# mega328_withheaders_andxbee_v2.net
KiCad netlist of a schematic drawn in EAGLE
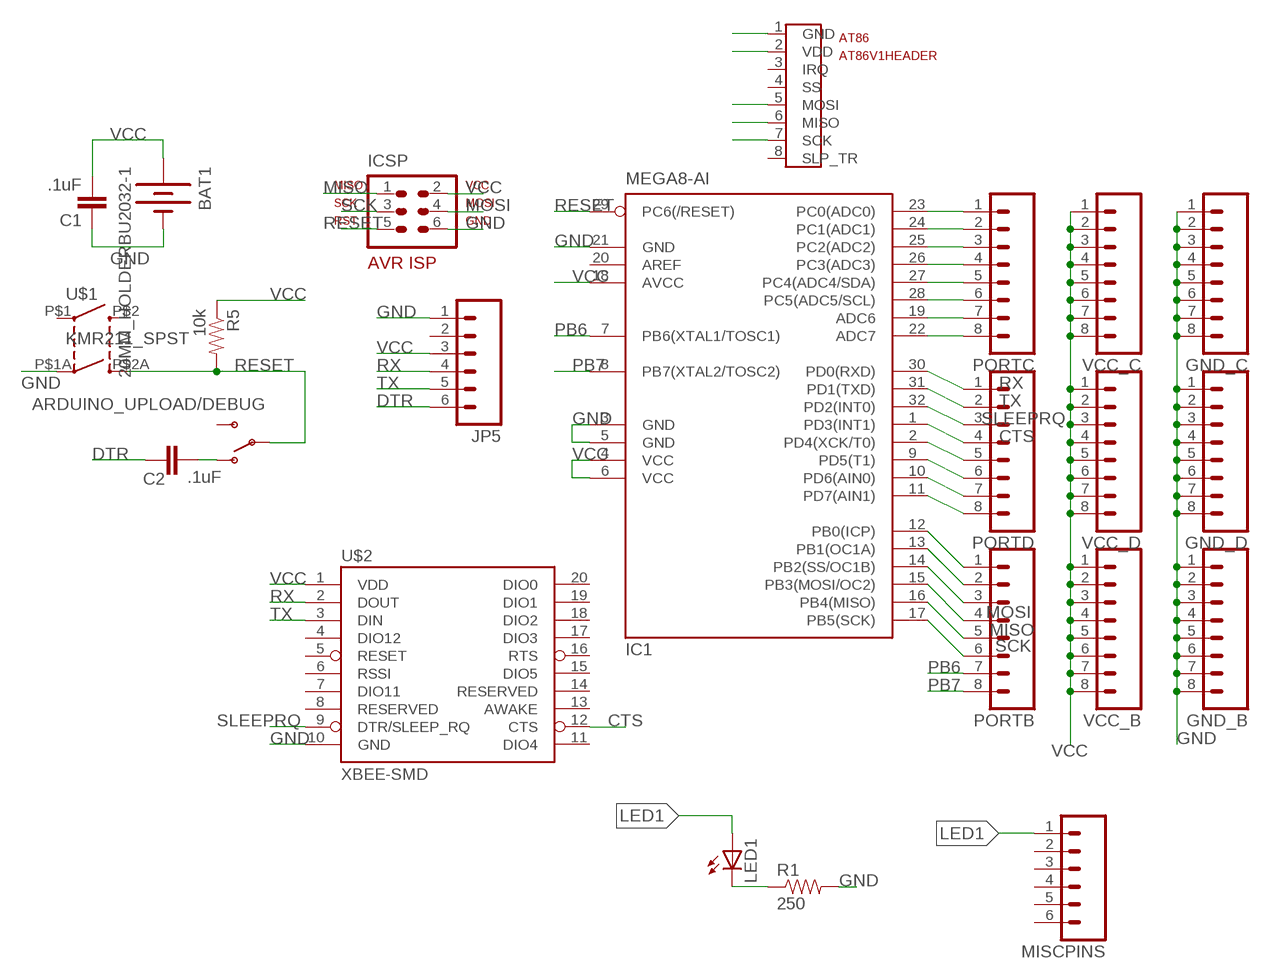
[diagram p0: schematic, sheet 1]

(export (version "E")
  (design (tool "Eeschema 10.0.6"))
  (components
    (comp (ref "ARDUINO_UPLOAD/DEBUG")
      (value "SWITCH-SPDT-SMD-A")
      (footprint "eagle-import:SWITCH-SPST-SMD-A")
      (libsource (lib "eagle-import") (part "SWITCH-SPDT-SMD-A"))
    )
    (comp (ref "AT86")
      (value "AT86V1HEADER")
      (footprint "eagle-import:AT86V1HEADER")
      (libsource (lib "eagle-import") (part "AT86V1HEADER"))
    )
    (comp (ref "BAT1")
      (value "20MM_HOLDERBU2032-1")
      (footprint "eagle-import:BU2032-1")
      (libsource (lib "eagle-import") (part "20MM_HOLDERBU2032-1"))
    )
    (comp (ref "C1")
      (value ".1uF")
      (footprint "eagle-import:0603-CAP")
      (libsource (lib "eagle-import") (part "CAP0603-CAP"))
    )
    (comp (ref "C2")
      (value ".1uF")
      (footprint "eagle-import:0603-CAP")
      (libsource (lib "eagle-import") (part "CAP0603-CAP"))
    )
    (comp (ref "GND_B")
      (value "M081X08")
      (footprint "eagle-import:1X08")
      (libsource (lib "eagle-import") (part "M081X08"))
    )
    (comp (ref "GND_C")
      (value "M081X08")
      (footprint "eagle-import:1X08")
      (libsource (lib "eagle-import") (part "M081X08"))
    )
    (comp (ref "GND_D")
      (value "M081X08")
      (footprint "eagle-import:1X08")
      (libsource (lib "eagle-import") (part "M081X08"))
    )
    (comp (ref "IC1")
      (value "MEGA8-AI")
      (footprint "eagle-import:TQFP32-08")
      (fields (field (name "MPN") "ATMEGA8-16AU"))
      (libsource (lib "eagle-import") (part "MEGA8-AI"))
    )
    (comp (ref "ICSP")
      (value "ISP")
      (footprint "eagle-import:AVR-ISP-6")
      (libsource (lib "eagle-import") (part "AVR-ISP-6VERT"))
    )
    (comp (ref "JP5")
      (value "M06SIP")
      (footprint "eagle-import:1X06")
      (libsource (lib "eagle-import") (part "M06SIP"))
    )
    (comp (ref "LED1")
      (value "LEDCHIP-LED0603")
      (footprint "eagle-import:CHIP-LED0603")
      (libsource (lib "eagle-import") (part "LEDCHIP-LED0603"))
    )
    (comp (ref "MISCPINS")
      (value "M06SIP")
      (footprint "eagle-import:1X06")
      (libsource (lib "eagle-import") (part "M06SIP"))
    )
    (comp (ref "PORTB")
      (value "M081X08")
      (footprint "eagle-import:1X08")
      (libsource (lib "eagle-import") (part "M081X08"))
    )
    (comp (ref "PORTC")
      (value "M081X08")
      (footprint "eagle-import:1X08")
      (libsource (lib "eagle-import") (part "M081X08"))
    )
    (comp (ref "PORTD")
      (value "M081X08")
      (footprint "eagle-import:1X08")
      (libsource (lib "eagle-import") (part "M081X08"))
    )
    (comp (ref "R1")
      (value "250")
      (footprint "eagle-import:0603-RES")
      (libsource (lib "eagle-import") (part "RESISTOR0603-RES"))
    )
    (comp (ref "R5")
      (value "10k")
      (footprint "eagle-import:0603-RES")
      (libsource (lib "eagle-import") (part "RESISTOR0603-RES"))
    )
    (comp (ref "U$1")
      (value "KMR211_SPST")
      (footprint "eagle-import:KMR211_SPST")
      (libsource (lib "eagle-import") (part "KMR211_SPST"))
    )
    (comp (ref "U$2")
      (value "XBEE-SMD")
      (footprint "eagle-import:XBEE-SMD")
      (libsource (lib "eagle-import") (part "XBEE-SMD"))
    )
    (comp (ref "VCC_B")
      (value "M081X08")
      (footprint "eagle-import:1X08")
      (libsource (lib "eagle-import") (part "M081X08"))
    )
    (comp (ref "VCC_C")
      (value "M081X08")
      (footprint "eagle-import:1X08")
      (libsource (lib "eagle-import") (part "M081X08"))
    )
    (comp (ref "VCC_D")
      (value "M081X08")
      (footprint "eagle-import:1X08")
      (libsource (lib "eagle-import") (part "M081X08"))
    )
  )
  (nets
    (net (code "1") (name "/CTS") (class "Default")
      (node (ref "IC1") (pin "1") (pinfunction "PD3(INT1)_1") (pintype "bidirectional"))
      (node (ref "PORTD") (pin "4") (pinfunction "4_4") (pintype "passive"))
      (node (ref "U$2") (pin "12") (pinfunction "CTS_12") (pintype "output"))
    )
    (net (code "2") (name "/DTR") (class "Default")
      (node (ref "C2") (pin "1") (pinfunction "1_1") (pintype "passive"))
      (node (ref "JP5") (pin "6") (pinfunction "6_6") (pintype "passive"))
    )
    (net (code "3") (name "/GND") (class "Default")
      (node (ref "AT86") (pin "1") (pinfunction "GND_1") (pintype "bidirectional"))
      (node (ref "BAT1") (pin "-") (pinfunction "-_-") (pintype "power_in"))
      (node (ref "C1") (pin "1") (pinfunction "1_1") (pintype "passive"))
      (node (ref "GND_B") (pin "1") (pinfunction "1_1") (pintype "passive"))
      (node (ref "GND_B") (pin "2") (pinfunction "2_2") (pintype "passive"))
      (node (ref "GND_B") (pin "3") (pinfunction "3_3") (pintype "passive"))
      (node (ref "GND_B") (pin "4") (pinfunction "4_4") (pintype "passive"))
      (node (ref "GND_B") (pin "5") (pinfunction "5_5") (pintype "passive"))
      (node (ref "GND_B") (pin "6") (pinfunction "6_6") (pintype "passive"))
      (node (ref "GND_B") (pin "7") (pinfunction "7_7") (pintype "passive"))
      (node (ref "GND_B") (pin "8") (pinfunction "8_8") (pintype "passive"))
      (node (ref "GND_C") (pin "1") (pinfunction "1_1") (pintype "passive"))
      (node (ref "GND_C") (pin "2") (pinfunction "2_2") (pintype "passive"))
      (node (ref "GND_C") (pin "3") (pinfunction "3_3") (pintype "passive"))
      (node (ref "GND_C") (pin "4") (pinfunction "4_4") (pintype "passive"))
      (node (ref "GND_C") (pin "5") (pinfunction "5_5") (pintype "passive"))
      (node (ref "GND_C") (pin "6") (pinfunction "6_6") (pintype "passive"))
      (node (ref "GND_C") (pin "7") (pinfunction "7_7") (pintype "passive"))
      (node (ref "GND_C") (pin "8") (pinfunction "8_8") (pintype "passive"))
      (node (ref "GND_D") (pin "1") (pinfunction "1_1") (pintype "passive"))
      (node (ref "GND_D") (pin "2") (pinfunction "2_2") (pintype "passive"))
      (node (ref "GND_D") (pin "3") (pinfunction "3_3") (pintype "passive"))
      (node (ref "GND_D") (pin "4") (pinfunction "4_4") (pintype "passive"))
      (node (ref "GND_D") (pin "5") (pinfunction "5_5") (pintype "passive"))
      (node (ref "GND_D") (pin "6") (pinfunction "6_6") (pintype "passive"))
      (node (ref "GND_D") (pin "7") (pinfunction "7_7") (pintype "passive"))
      (node (ref "GND_D") (pin "8") (pinfunction "8_8") (pintype "passive"))
      (node (ref "IC1") (pin "21") (pinfunction "GND_21") (pintype "power_in"))
      (node (ref "IC1") (pin "3") (pinfunction "GND_3") (pintype "power_in"))
      (node (ref "IC1") (pin "5") (pinfunction "GND_5") (pintype "power_in"))
      (node (ref "ICSP") (pin "6") (pinfunction "6_6") (pintype "passive"))
      (node (ref "JP5") (pin "1") (pinfunction "1_1") (pintype "passive"))
      (node (ref "R1") (pin "2") (pinfunction "2_2") (pintype "passive"))
      (node (ref "U$1") (pin "P$1A") (pinfunction "1B_P$1A") (pintype "passive"))
      (node (ref "U$2") (pin "10") (pinfunction "GND_10") (pintype "power_in"))
    )
    (net (code "4") (name "/MISO") (class "Default")
      (node (ref "AT86") (pin "6") (pinfunction "MISO_6") (pintype "bidirectional"))
      (node (ref "IC1") (pin "16") (pinfunction "PB4(MISO)_16") (pintype "bidirectional"))
      (node (ref "ICSP") (pin "1") (pinfunction "1_1") (pintype "passive"))
      (node (ref "PORTB") (pin "5") (pinfunction "5_5") (pintype "passive"))
    )
    (net (code "5") (name "/MOSI") (class "Default")
      (node (ref "AT86") (pin "5") (pinfunction "MOSI_5") (pintype "bidirectional"))
      (node (ref "IC1") (pin "15") (pinfunction "PB3(MOSI/OC2)_15") (pintype "bidirectional"))
      (node (ref "ICSP") (pin "4") (pinfunction "4_4") (pintype "passive"))
      (node (ref "PORTB") (pin "4") (pinfunction "4_4") (pintype "passive"))
    )
    (net (code "6") (name "/PB6") (class "Default")
      (node (ref "IC1") (pin "7") (pinfunction "PB6(XTAL1/TOSC1)_7") (pintype "bidirectional"))
      (node (ref "PORTB") (pin "7") (pinfunction "7_7") (pintype "passive"))
    )
    (net (code "7") (name "/PB7") (class "Default")
      (node (ref "IC1") (pin "8") (pinfunction "PB7(XTAL2/TOSC2)_8") (pintype "bidirectional"))
      (node (ref "PORTB") (pin "8") (pinfunction "8_8") (pintype "passive"))
    )
    (net (code "8") (name "/RESET") (class "Default")
      (node (ref "ARDUINO_UPLOAD/DEBUG") (pin "2") (pinfunction "P_2") (pintype "passive"))
      (node (ref "IC1") (pin "29") (pinfunction "PC6(/RESET)_29") (pintype "bidirectional"))
      (node (ref "ICSP") (pin "5") (pinfunction "5_5") (pintype "passive"))
      (node (ref "R5") (pin "2") (pinfunction "2_2") (pintype "passive"))
      (node (ref "U$1") (pin "P$2A") (pinfunction "2B_P$2A") (pintype "passive"))
    )
    (net (code "9") (name "/RX") (class "Default")
      (node (ref "IC1") (pin "30") (pinfunction "PD0(RXD)_30") (pintype "bidirectional"))
      (node (ref "JP5") (pin "4") (pinfunction "4_4") (pintype "passive"))
      (node (ref "PORTD") (pin "1") (pinfunction "1_1") (pintype "passive"))
      (node (ref "U$2") (pin "2") (pinfunction "DOUT_2") (pintype "output"))
    )
    (net (code "10") (name "/SCK") (class "Default")
      (node (ref "AT86") (pin "7") (pinfunction "SCK_7") (pintype "bidirectional"))
      (node (ref "IC1") (pin "17") (pinfunction "PB5(SCK)_17") (pintype "bidirectional"))
      (node (ref "ICSP") (pin "3") (pinfunction "3_3") (pintype "passive"))
      (node (ref "PORTB") (pin "6") (pinfunction "6_6") (pintype "passive"))
    )
    (net (code "11") (name "/SLEEPRQ") (class "Default")
      (node (ref "IC1") (pin "32") (pinfunction "PD2(INT0)_32") (pintype "bidirectional"))
      (node (ref "PORTD") (pin "3") (pinfunction "3_3") (pintype "passive"))
      (node (ref "U$2") (pin "9") (pinfunction "DTR/SLEEP_RQ_9") (pintype "bidirectional"))
    )
    (net (code "12") (name "/TX") (class "Default")
      (node (ref "IC1") (pin "31") (pinfunction "PD1(TXD)_31") (pintype "bidirectional"))
      (node (ref "JP5") (pin "5") (pinfunction "5_5") (pintype "passive"))
      (node (ref "PORTD") (pin "2") (pinfunction "2_2") (pintype "passive"))
      (node (ref "U$2") (pin "3") (pinfunction "DIN_3") (pintype "input"))
    )
    (net (code "13") (name "/VCC") (class "Default")
      (node (ref "AT86") (pin "2") (pinfunction "VDD_2") (pintype "bidirectional"))
      (node (ref "BAT1") (pin "+@1") (pinfunction "+_+@1") (pintype "power_in"))
      (node (ref "BAT1") (pin "+@2") (pinfunction "+_+@2") (pintype "power_in"))
      (node (ref "C1") (pin "2") (pinfunction "2_2") (pintype "passive"))
      (node (ref "IC1") (pin "18") (pinfunction "AVCC_18") (pintype "power_in"))
      (node (ref "IC1") (pin "4") (pinfunction "VCC_4") (pintype "power_in"))
      (node (ref "IC1") (pin "6") (pinfunction "VCC_6") (pintype "power_in"))
      (node (ref "ICSP") (pin "2") (pinfunction "2_2") (pintype "passive"))
      (node (ref "JP5") (pin "3") (pinfunction "3_3") (pintype "passive"))
      (node (ref "R5") (pin "1") (pinfunction "1_1") (pintype "passive"))
      (node (ref "U$2") (pin "1") (pinfunction "VDD_1") (pintype "power_in"))
      (node (ref "VCC_B") (pin "1") (pinfunction "1_1") (pintype "passive"))
      (node (ref "VCC_B") (pin "2") (pinfunction "2_2") (pintype "passive"))
      (node (ref "VCC_B") (pin "3") (pinfunction "3_3") (pintype "passive"))
      (node (ref "VCC_B") (pin "4") (pinfunction "4_4") (pintype "passive"))
      (node (ref "VCC_B") (pin "5") (pinfunction "5_5") (pintype "passive"))
      (node (ref "VCC_B") (pin "6") (pinfunction "6_6") (pintype "passive"))
      (node (ref "VCC_B") (pin "7") (pinfunction "7_7") (pintype "passive"))
      (node (ref "VCC_B") (pin "8") (pinfunction "8_8") (pintype "passive"))
      (node (ref "VCC_C") (pin "1") (pinfunction "1_1") (pintype "passive"))
      (node (ref "VCC_C") (pin "2") (pinfunction "2_2") (pintype "passive"))
      (node (ref "VCC_C") (pin "3") (pinfunction "3_3") (pintype "passive"))
      (node (ref "VCC_C") (pin "4") (pinfunction "4_4") (pintype "passive"))
      (node (ref "VCC_C") (pin "5") (pinfunction "5_5") (pintype "passive"))
      (node (ref "VCC_C") (pin "6") (pinfunction "6_6") (pintype "passive"))
      (node (ref "VCC_C") (pin "7") (pinfunction "7_7") (pintype "passive"))
      (node (ref "VCC_C") (pin "8") (pinfunction "8_8") (pintype "passive"))
      (node (ref "VCC_D") (pin "1") (pinfunction "1_1") (pintype "passive"))
      (node (ref "VCC_D") (pin "2") (pinfunction "2_2") (pintype "passive"))
      (node (ref "VCC_D") (pin "3") (pinfunction "3_3") (pintype "passive"))
      (node (ref "VCC_D") (pin "4") (pinfunction "4_4") (pintype "passive"))
      (node (ref "VCC_D") (pin "5") (pinfunction "5_5") (pintype "passive"))
      (node (ref "VCC_D") (pin "6") (pinfunction "6_6") (pintype "passive"))
      (node (ref "VCC_D") (pin "7") (pinfunction "7_7") (pintype "passive"))
      (node (ref "VCC_D") (pin "8") (pinfunction "8_8") (pintype "passive"))
    )
    (net (code "14") (name "LED1") (class "Default")
      (node (ref "LED1") (pin "A") (pinfunction "A_A") (pintype "passive"))
      (node (ref "MISCPINS") (pin "1") (pinfunction "1_1") (pintype "passive"))
    )
    (net (code "15") (name "Net-(ARDUINO_UPLOAD/DEBUG-O)") (class "Default")
      (node (ref "ARDUINO_UPLOAD/DEBUG") (pin "1") (pinfunction "O_1") (pintype "passive"))
      (node (ref "C2") (pin "2") (pinfunction "2_2") (pintype "passive"))
    )
    (net (code "16") (name "Net-(IC1-ADC6)") (class "Default")
      (node (ref "IC1") (pin "19") (pinfunction "ADC6_19") (pintype "bidirectional"))
      (node (ref "PORTC") (pin "7") (pinfunction "7_7") (pintype "passive"))
    )
    (net (code "17") (name "Net-(IC1-ADC7)") (class "Default")
      (node (ref "IC1") (pin "22") (pinfunction "ADC7_22") (pintype "bidirectional"))
      (node (ref "PORTC") (pin "8") (pinfunction "8_8") (pintype "passive"))
    )
    (net (code "18") (name "Net-(IC1-PB0(ICP))") (class "Default")
      (node (ref "IC1") (pin "12") (pinfunction "PB0(ICP)_12") (pintype "bidirectional"))
      (node (ref "PORTB") (pin "1") (pinfunction "1_1") (pintype "passive"))
    )
    (net (code "19") (name "Net-(IC1-PB1(OC1A))") (class "Default")
      (node (ref "IC1") (pin "13") (pinfunction "PB1(OC1A)_13") (pintype "bidirectional"))
      (node (ref "PORTB") (pin "2") (pinfunction "2_2") (pintype "passive"))
    )
    (net (code "20") (name "Net-(IC1-PB2(SS{slash}OC1B))") (class "Default")
      (node (ref "IC1") (pin "14") (pinfunction "PB2(SS/OC1B)_14") (pintype "bidirectional"))
      (node (ref "PORTB") (pin "3") (pinfunction "3_3") (pintype "passive"))
    )
    (net (code "21") (name "Net-(IC1-PC0(ADC0))") (class "Default")
      (node (ref "IC1") (pin "23") (pinfunction "PC0(ADC0)_23") (pintype "bidirectional"))
      (node (ref "PORTC") (pin "1") (pinfunction "1_1") (pintype "passive"))
    )
    (net (code "22") (name "Net-(IC1-PC1(ADC1))") (class "Default")
      (node (ref "IC1") (pin "24") (pinfunction "PC1(ADC1)_24") (pintype "bidirectional"))
      (node (ref "PORTC") (pin "2") (pinfunction "2_2") (pintype "passive"))
    )
    (net (code "23") (name "Net-(IC1-PC2(ADC2))") (class "Default")
      (node (ref "IC1") (pin "25") (pinfunction "PC2(ADC2)_25") (pintype "bidirectional"))
      (node (ref "PORTC") (pin "3") (pinfunction "3_3") (pintype "passive"))
    )
    (net (code "24") (name "Net-(IC1-PC3(ADC3))") (class "Default")
      (node (ref "IC1") (pin "26") (pinfunction "PC3(ADC3)_26") (pintype "bidirectional"))
      (node (ref "PORTC") (pin "4") (pinfunction "4_4") (pintype "passive"))
    )
    (net (code "25") (name "Net-(IC1-PC4(ADC4{slash}SDA))") (class "Default")
      (node (ref "IC1") (pin "27") (pinfunction "PC4(ADC4/SDA)_27") (pintype "bidirectional"))
      (node (ref "PORTC") (pin "5") (pinfunction "5_5") (pintype "passive"))
    )
    (net (code "26") (name "Net-(IC1-PC5(ADC5{slash}SCL))") (class "Default")
      (node (ref "IC1") (pin "28") (pinfunction "PC5(ADC5/SCL)_28") (pintype "bidirectional"))
      (node (ref "PORTC") (pin "6") (pinfunction "6_6") (pintype "passive"))
    )
    (net (code "27") (name "Net-(IC1-PD4(XCK{slash}T0))") (class "Default")
      (node (ref "IC1") (pin "2") (pinfunction "PD4(XCK/T0)_2") (pintype "bidirectional"))
      (node (ref "PORTD") (pin "5") (pinfunction "5_5") (pintype "passive"))
    )
    (net (code "28") (name "Net-(IC1-PD5(T1))") (class "Default")
      (node (ref "IC1") (pin "9") (pinfunction "PD5(T1)_9") (pintype "bidirectional"))
      (node (ref "PORTD") (pin "6") (pinfunction "6_6") (pintype "passive"))
    )
    (net (code "29") (name "Net-(IC1-PD6(AIN0))") (class "Default")
      (node (ref "IC1") (pin "10") (pinfunction "PD6(AIN0)_10") (pintype "bidirectional"))
      (node (ref "PORTD") (pin "7") (pinfunction "7_7") (pintype "passive"))
    )
    (net (code "30") (name "Net-(IC1-PD7(AIN1))") (class "Default")
      (node (ref "IC1") (pin "11") (pinfunction "PD7(AIN1)_11") (pintype "bidirectional"))
      (node (ref "PORTD") (pin "8") (pinfunction "8_8") (pintype "passive"))
    )
    (net (code "31") (name "Net-(LED1-PadC)") (class "Default")
      (node (ref "LED1") (pin "C") (pinfunction "C_C") (pintype "passive"))
      (node (ref "R1") (pin "1") (pinfunction "1_1") (pintype "passive"))
    )
    (net (code "32") (name "unconnected-(ARDUINO_UPLOAD/DEBUG-S-Pad3)") (class "Default")
      (node (ref "ARDUINO_UPLOAD/DEBUG") (pin "3") (pinfunction "S_3") (pintype "passive"))
    )
    (net (code "33") (name "unconnected-(AT86-IRQ-Pad3)") (class "Default")
      (node (ref "AT86") (pin "3") (pinfunction "IRQ_3") (pintype "bidirectional"))
    )
    (net (code "34") (name "unconnected-(AT86-SLP_TR-Pad8)") (class "Default")
      (node (ref "AT86") (pin "8") (pinfunction "SLP_TR_8") (pintype "bidirectional"))
    )
    (net (code "35") (name "unconnected-(AT86-SS-Pad4)") (class "Default")
      (node (ref "AT86") (pin "4") (pinfunction "SS_4") (pintype "bidirectional"))
    )
    (net (code "36") (name "unconnected-(IC1-AREF-Pad20)") (class "Default")
      (node (ref "IC1") (pin "20") (pinfunction "AREF_20") (pintype "passive"))
    )
    (net (code "37") (name "unconnected-(JP5-Pad2)") (class "Default")
      (node (ref "JP5") (pin "2") (pinfunction "2_2") (pintype "passive"))
    )
    (net (code "38") (name "unconnected-(MISCPINS-Pad2)") (class "Default")
      (node (ref "MISCPINS") (pin "2") (pinfunction "2_2") (pintype "passive"))
    )
    (net (code "39") (name "unconnected-(MISCPINS-Pad3)") (class "Default")
      (node (ref "MISCPINS") (pin "3") (pinfunction "3_3") (pintype "passive"))
    )
    (net (code "40") (name "unconnected-(MISCPINS-Pad4)") (class "Default")
      (node (ref "MISCPINS") (pin "4") (pinfunction "4_4") (pintype "passive"))
    )
    (net (code "41") (name "unconnected-(MISCPINS-Pad5)") (class "Default")
      (node (ref "MISCPINS") (pin "5") (pinfunction "5_5") (pintype "passive"))
    )
    (net (code "42") (name "unconnected-(MISCPINS-Pad6)") (class "Default")
      (node (ref "MISCPINS") (pin "6") (pinfunction "6_6") (pintype "passive"))
    )
    (net (code "43") (name "unconnected-(U$1-1A-PadP$1)") (class "Default")
      (node (ref "U$1") (pin "P$1") (pinfunction "1A_P$1") (pintype "no_connect"))
    )
    (net (code "44") (name "unconnected-(U$1-2A-PadP$2)") (class "Default")
      (node (ref "U$1") (pin "P$2") (pinfunction "2A_P$2") (pintype "no_connect"))
    )
    (net (code "45") (name "unconnected-(U$2-AWAKE-Pad13)") (class "Default")
      (node (ref "U$2") (pin "13") (pinfunction "AWAKE_13") (pintype "bidirectional"))
    )
    (net (code "46") (name "unconnected-(U$2-DIO0-Pad20)") (class "Default")
      (node (ref "U$2") (pin "20") (pinfunction "DIO0_20") (pintype "bidirectional"))
    )
    (net (code "47") (name "unconnected-(U$2-DIO1-Pad19)") (class "Default")
      (node (ref "U$2") (pin "19") (pinfunction "DIO1_19") (pintype "bidirectional"))
    )
    (net (code "48") (name "unconnected-(U$2-DIO2-Pad18)") (class "Default")
      (node (ref "U$2") (pin "18") (pinfunction "DIO2_18") (pintype "bidirectional"))
    )
    (net (code "49") (name "unconnected-(U$2-DIO3-Pad17)") (class "Default")
      (node (ref "U$2") (pin "17") (pinfunction "DIO3_17") (pintype "bidirectional"))
    )
    (net (code "50") (name "unconnected-(U$2-DIO4-Pad11)") (class "Default")
      (node (ref "U$2") (pin "11") (pinfunction "DIO4_11") (pintype "bidirectional"))
    )
    (net (code "51") (name "unconnected-(U$2-DIO5-Pad15)") (class "Default")
      (node (ref "U$2") (pin "15") (pinfunction "DIO5_15") (pintype "bidirectional"))
    )
    (net (code "52") (name "unconnected-(U$2-DIO11-Pad7)") (class "Default")
      (node (ref "U$2") (pin "7") (pinfunction "DIO11_7") (pintype "bidirectional"))
    )
    (net (code "53") (name "unconnected-(U$2-DIO12-Pad4)") (class "Default")
      (node (ref "U$2") (pin "4") (pinfunction "DIO12_4") (pintype "bidirectional"))
    )
    (net (code "54") (name "unconnected-(U$2-RESERVED-Pad8)") (class "Default")
      (node (ref "U$2") (pin "8") (pinfunction "RESERVED_8") (pintype "bidirectional"))
    )
    (net (code "55") (name "unconnected-(U$2-RESERVED-Pad14)") (class "Default")
      (node (ref "U$2") (pin "14") (pinfunction "RESERVED_14") (pintype "bidirectional"))
    )
    (net (code "56") (name "unconnected-(U$2-RESET-Pad5)") (class "Default")
      (node (ref "U$2") (pin "5") (pinfunction "RESET_5") (pintype "input"))
    )
    (net (code "57") (name "unconnected-(U$2-RSSI-Pad6)") (class "Default")
      (node (ref "U$2") (pin "6") (pinfunction "RSSI_6") (pintype "bidirectional"))
    )
    (net (code "58") (name "unconnected-(U$2-RTS-Pad16)") (class "Default")
      (node (ref "U$2") (pin "16") (pinfunction "RTS_16") (pintype "input"))
    )
  )
)
